# electroplating.net
KiCad netlist of a schematic drawn in EAGLE
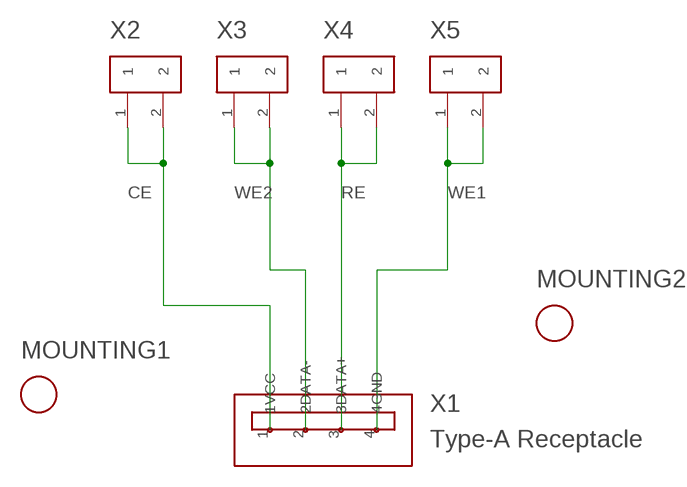
[diagram p0: schematic, sheet 1]

(export (version "E")
  (design (tool "Eeschema 10.0.6"))
  (components
    (comp (ref "MOUNTING1")
      (value "M2-MOUNTING-HOLE")
      (footprint "eagle-import:M2-MOUNTING-HOLE")
      (libsource (lib "eagle-import") (part "M2-MOUNTING-HOLE"))
    )
    (comp (ref "MOUNTING2")
      (value "M2-MOUNTING-HOLE")
      (footprint "eagle-import:M2-MOUNTING-HOLE")
      (libsource (lib "eagle-import") (part "M2-MOUNTING-HOLE"))
    )
    (comp (ref "X1")
      (value "Type-A Receptacle")
      (footprint "eagle-import:TE_CONNECTIVITY_292303-1")
      (libsource (lib "eagle-import") (part "USB-TYPE-A-RECEPTACLE"))
    )
    (comp (ref "X2")
      (value "2-PIN-CONNECTOR")
      (footprint "eagle-import:2-PIN-HEADER")
      (libsource (lib "eagle-import") (part "2-PIN-CONNECTOR"))
    )
    (comp (ref "X3")
      (value "2-PIN-CONNECTOR")
      (footprint "eagle-import:2-PIN-HEADER")
      (libsource (lib "eagle-import") (part "2-PIN-CONNECTOR"))
    )
    (comp (ref "X4")
      (value "2-PIN-CONNECTOR")
      (footprint "eagle-import:2-PIN-HEADER")
      (libsource (lib "eagle-import") (part "2-PIN-CONNECTOR"))
    )
    (comp (ref "X5")
      (value "2-PIN-CONNECTOR")
      (footprint "eagle-import:2-PIN-HEADER")
      (libsource (lib "eagle-import") (part "2-PIN-CONNECTOR"))
    )
  )
  (nets
    (net (code "1") (name "/CE") (class "Default")
      (node (ref "X1") (pin "1") (pinfunction "1VCC_1") (pintype "bidirectional"))
      (node (ref "X2") (pin "1") (pinfunction "1_1") (pintype "bidirectional"))
      (node (ref "X2") (pin "2") (pinfunction "2_2") (pintype "bidirectional"))
    )
    (net (code "2") (name "/RE") (class "Default")
      (node (ref "X1") (pin "3") (pinfunction "3DATA+_3") (pintype "bidirectional"))
      (node (ref "X4") (pin "1") (pinfunction "1_1") (pintype "bidirectional"))
      (node (ref "X4") (pin "2") (pinfunction "2_2") (pintype "bidirectional"))
    )
    (net (code "3") (name "/WE1") (class "Default")
      (node (ref "X1") (pin "4") (pinfunction "4GND_4") (pintype "bidirectional"))
      (node (ref "X5") (pin "1") (pinfunction "1_1") (pintype "bidirectional"))
      (node (ref "X5") (pin "2") (pinfunction "2_2") (pintype "bidirectional"))
    )
    (net (code "4") (name "/WE2") (class "Default")
      (node (ref "X1") (pin "2") (pinfunction "2DATA-_2") (pintype "bidirectional"))
      (node (ref "X3") (pin "1") (pinfunction "1_1") (pintype "bidirectional"))
      (node (ref "X3") (pin "2") (pinfunction "2_2") (pintype "bidirectional"))
    )
  )
)
